# ttl2rs232.net
KiCad netlist of a schematic drawn in Altium Designer
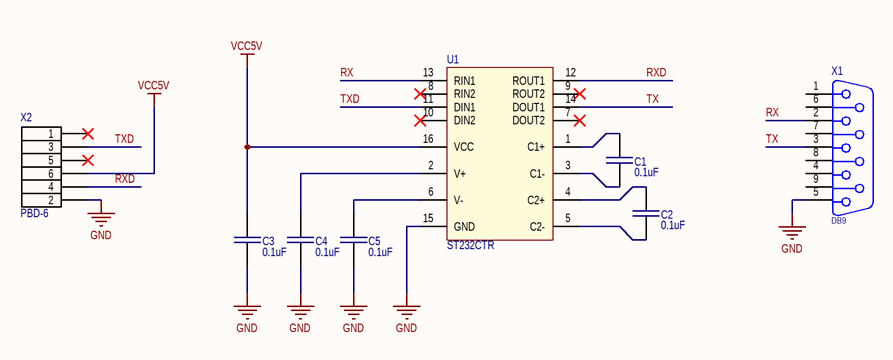
[diagram p0: ttl2rs232.SchDoc]

(export (version "E")
  (design (tool "Eeschema 10.0.6"))
  (components
    (comp (ref "C1")
      (value "0.1uF")
      (footprint "C_0603")
      (description "Capacitor")
      (fields (field (name "PART NUMBER") "CC0603KPX7R9BB104"))
      (libsource (lib "capacitors") (part "C0603"))
    )
    (comp (ref "C2")
      (value "0.1uF")
      (footprint "C_0603")
      (description "Capacitor")
      (fields (field (name "PART NUMBER") "CC0603KPX7R9BB104"))
      (libsource (lib "capacitors") (part "C0603"))
    )
    (comp (ref "C3")
      (value "0.1uF")
      (footprint "C_0603")
      (description "Capacitor")
      (fields (field (name "PART NUMBER") "CC0603KPX7R9BB104"))
      (libsource (lib "capacitors") (part "C0603"))
    )
    (comp (ref "C4")
      (value "0.1uF")
      (footprint "C_0603")
      (description "Capacitor")
      (fields (field (name "PART NUMBER") "CC0603KPX7R9BB104"))
      (libsource (lib "capacitors") (part "C0603"))
    )
    (comp (ref "C5")
      (value "0.1uF")
      (footprint "C_0603")
      (description "Capacitor")
      (fields (field (name "PART NUMBER") "CC0603KPX7R9BB104"))
      (libsource (lib "capacitors") (part "C0603"))
    )
    (comp (ref "U1")
      (value "ST232CTR")
      (footprint "TSSOP16_STM")
      (description "No Description Available")
      (fields (field (name "COPYRIGHT") "Copyright (C) 2022 Ultra Librarian. All rights reserved."))
      (libsource (lib "discret_ic") (part "ST232CTR"))
    )
    (comp (ref "X1")
      (value "DB9")
      (footprint "DB9_template")
      (description "Connector")
      (libsource (lib "connectors_socets") (part "DB9_template"))
    )
    (comp (ref "X2")
      (value "PBD-6")
      (footprint "PBD-6-sideways")
      (description "Header, 6-Pin, Dual row")
      (libsource (lib "connectors_socets") (part "PBD-6"))
    )
  )
  (nets
    (net (code "1") (name "/RX") (class "Default")
      (node (ref "U1") (pin "13") (pinfunction "RIN1_13") (pintype "passive"))
      (node (ref "X1") (pin "2") (pinfunction "2_2") (pintype "passive"))
    )
    (net (code "2") (name "/RXD") (class "Default")
      (node (ref "U1") (pin "12") (pinfunction "ROUT1_12") (pintype "passive"))
      (node (ref "X2") (pin "4") (pinfunction "4_4") (pintype "passive"))
    )
    (net (code "3") (name "/TX") (class "Default")
      (node (ref "U1") (pin "14") (pinfunction "DOUT1_14") (pintype "passive"))
      (node (ref "X1") (pin "3") (pinfunction "3_3") (pintype "passive"))
    )
    (net (code "4") (name "/TXD") (class "Default")
      (node (ref "U1") (pin "11") (pinfunction "DIN1_11") (pintype "passive"))
      (node (ref "X2") (pin "3") (pinfunction "3_3") (pintype "passive"))
    )
    (net (code "5") (name "GND") (class "Default")
      (node (ref "C3") (pin "1") (pinfunction "1_1") (pintype "passive"))
      (node (ref "C4") (pin "1") (pinfunction "1_1") (pintype "passive"))
      (node (ref "C5") (pin "1") (pinfunction "1_1") (pintype "passive"))
      (node (ref "U1") (pin "15") (pinfunction "GND_15") (pintype "passive"))
      (node (ref "X1") (pin "5") (pinfunction "5_5") (pintype "passive"))
      (node (ref "X2") (pin "2") (pinfunction "2_2") (pintype "passive"))
    )
    (net (code "6") (name "Net-(U1-C1+)") (class "Default")
      (node (ref "C1") (pin "1") (pinfunction "1_1") (pintype "passive"))
      (node (ref "U1") (pin "1") (pinfunction "C1+_1") (pintype "passive"))
    )
    (net (code "7") (name "Net-(U1-C1-)") (class "Default")
      (node (ref "C1") (pin "2") (pinfunction "2_2") (pintype "passive"))
      (node (ref "U1") (pin "3") (pinfunction "C1-_3") (pintype "passive"))
    )
    (net (code "8") (name "Net-(U1-C2+)") (class "Default")
      (node (ref "C2") (pin "1") (pinfunction "1_1") (pintype "passive"))
      (node (ref "U1") (pin "4") (pinfunction "C2+_4") (pintype "passive"))
    )
    (net (code "9") (name "Net-(U1-C2-)") (class "Default")
      (node (ref "C2") (pin "2") (pinfunction "2_2") (pintype "passive"))
      (node (ref "U1") (pin "5") (pinfunction "C2-_5") (pintype "passive"))
    )
    (net (code "10") (name "Net-(U1-V+)") (class "Default")
      (node (ref "C4") (pin "2") (pinfunction "2_2") (pintype "passive"))
      (node (ref "U1") (pin "2") (pinfunction "V+_2") (pintype "passive"))
    )
    (net (code "11") (name "Net-(U1-V-)") (class "Default")
      (node (ref "C5") (pin "2") (pinfunction "2_2") (pintype "passive"))
      (node (ref "U1") (pin "6") (pinfunction "V-_6") (pintype "passive"))
    )
    (net (code "12") (name "VCC5V") (class "Default")
      (node (ref "C3") (pin "2") (pinfunction "2_2") (pintype "passive"))
      (node (ref "U1") (pin "16") (pinfunction "VCC_16") (pintype "passive"))
      (node (ref "X2") (pin "6") (pinfunction "6_6") (pintype "passive"))
    )
    (net (code "13") (name "unconnected-(U1-DIN2-Pad10)") (class "Default")
      (node (ref "U1") (pin "10") (pinfunction "DIN2_10") (pintype "passive+no_connect"))
    )
    (net (code "14") (name "unconnected-(U1-DOUT2-Pad7)") (class "Default")
      (node (ref "U1") (pin "7") (pinfunction "DOUT2_7") (pintype "passive+no_connect"))
    )
    (net (code "15") (name "unconnected-(U1-RIN2-Pad8)") (class "Default")
      (node (ref "U1") (pin "8") (pinfunction "RIN2_8") (pintype "passive+no_connect"))
    )
    (net (code "16") (name "unconnected-(U1-ROUT2-Pad9)") (class "Default")
      (node (ref "U1") (pin "9") (pinfunction "ROUT2_9") (pintype "passive+no_connect"))
    )
    (net (code "17") (name "unconnected-(X1-Pad1)") (class "Default")
      (node (ref "X1") (pin "1") (pinfunction "1_1") (pintype "passive"))
    )
    (net (code "18") (name "unconnected-(X1-Pad4)") (class "Default")
      (node (ref "X1") (pin "4") (pinfunction "4_4") (pintype "passive"))
    )
    (net (code "19") (name "unconnected-(X1-Pad6)") (class "Default")
      (node (ref "X1") (pin "6") (pinfunction "6_6") (pintype "passive"))
    )
    (net (code "20") (name "unconnected-(X1-Pad7)") (class "Default")
      (node (ref "X1") (pin "7") (pinfunction "7_7") (pintype "passive"))
    )
    (net (code "21") (name "unconnected-(X1-Pad8)") (class "Default")
      (node (ref "X1") (pin "8") (pinfunction "8_8") (pintype "passive"))
    )
    (net (code "22") (name "unconnected-(X1-Pad9)") (class "Default")
      (node (ref "X1") (pin "9") (pinfunction "9_9") (pintype "passive"))
    )
    (net (code "23") (name "unconnected-(X2-Pad1)") (class "Default")
      (node (ref "X2") (pin "1") (pinfunction "1_1") (pintype "passive+no_connect"))
    )
    (net (code "24") (name "unconnected-(X2-Pad5)") (class "Default")
      (node (ref "X2") (pin "5") (pinfunction "5_5") (pintype "passive+no_connect"))
    )
  )
)
